# illuminated_button.net
KiCad netlist of a schematic drawn in Altium Designer
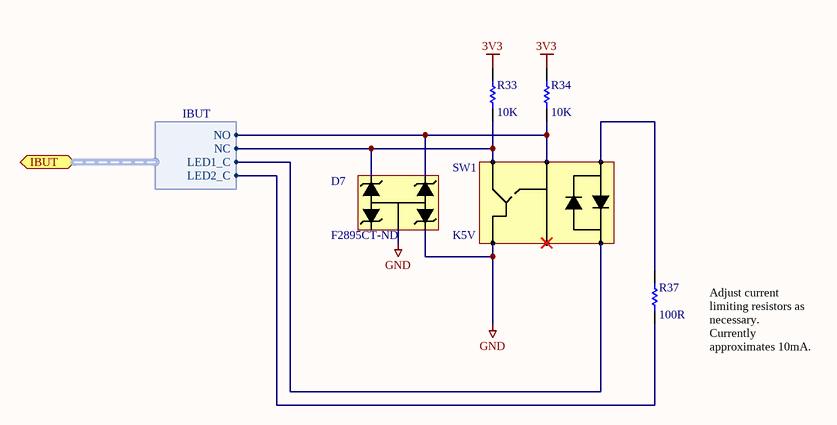
[diagram p0: illuminated_button.SchDoc]

(export (version "E")
  (design (tool "Eeschema 10.0.6"))
  (components
    (comp (ref "D7")
      (value "SP1001-04")
      (footprint "SC70-5")
      (description "8pF 15kV Unidirectional TVS Array 0.5uA@5.5V")
      (fields
        (field (name "SUPPLIER PART NUMBER 1") "F2895CT-ND")
        (field (name "MANUFACTURER") "Littelfuse Inc")
        (field (name "MANUFACTURER PART NUMBER") "SP1001-04JTG")
      )
      (libsource (lib "steve") (part "SP1001-04"))
    )
    (comp (ref "R33")
      (value "10K")
      (footprint "0603")
      (description "Semiconductor Resistor")
      (fields
        (field (name "MANUFACTURER") "TE Connectivity")
        (field (name "MANUFACTURER PART NUMBER") "1622829-1")
        (field (name "PUBLISHER") "Altium Limited")
      )
      (libsource (lib "Miscellaneous Devices") (part "Res Semi"))
    )
    (comp (ref "R34")
      (value "10K")
      (footprint "0603")
      (description "Semiconductor Resistor")
      (fields
        (field (name "MANUFACTURER") "TE Connectivity")
        (field (name "MANUFACTURER PART NUMBER") "1622829-1")
        (field (name "PUBLISHER") "Altium Limited")
      )
      (libsource (lib "Miscellaneous Devices") (part "Res Semi"))
    )
    (comp (ref "R37")
      (value "100R")
      (footprint "0603")
      (description "Semiconductor Resistor")
      (fields
        (field (name "MANUFACTURER") "Panasonic Electronic Components")
        (field (name "MANUFACTURER PART NUMBER") "ERJ-3EKF1000V")
        (field (name "PUBLISHER") "Altium Limited")
      )
      (libsource (lib "Miscellaneous Devices") (part "Res Semi"))
    )
    (comp (ref "SW1")
      (value "K5V")
      (footprint "K5V_PM")
      (description "K5V Illuminated Tactile Switch")
      (libsource (lib "steve") (part "K5V"))
    )
  )
  (nets
    (net (code "2") (name "/LED1_C") (class "Default")
      (node (ref "SW1") (pin "6") (pinfunction "6_6") (pintype "passive"))
    )
    (net (code "3") (name "/LED2_C") (class "Default")
      (node (ref "R37") (pin "1") (pinfunction "1_1") (pintype "passive"))
    )
    (net (code "4") (name "/NC") (class "Default")
      (node (ref "D7") (pin "5") (pinfunction "5_5") (pintype "passive"))
      (node (ref "R33") (pin "1") (pinfunction "1_1") (pintype "passive"))
      (node (ref "SW1") (pin "1") (pinfunction "1_1") (pintype "passive"))
    )
    (net (code "5") (name "/NO") (class "Default")
      (node (ref "D7") (pin "4") (pinfunction "4_4") (pintype "passive"))
      (node (ref "R34") (pin "1") (pinfunction "1_1") (pintype "passive"))
      (node (ref "SW1") (pin "3") (pinfunction "3_3") (pintype "passive"))
    )
    (net (code "7") (name "3V3") (class "Default")
      (node (ref "R33") (pin "2") (pinfunction "2_2") (pintype "passive"))
      (node (ref "R34") (pin "2") (pinfunction "2_2") (pintype "passive"))
    )
    (net (code "8") (name "GND") (class "Default")
      (node (ref "D7") (pin "2") (pinfunction "2_2") (pintype "passive"))
      (node (ref "D7") (pin "3") (pinfunction "3_3") (pintype "passive"))
      (node (ref "SW1") (pin "2") (pinfunction "2_2") (pintype "passive"))
    )
    (net (code "9") (name "Net-(R37-Pad2)") (class "Default")
      (node (ref "R37") (pin "2") (pinfunction "2_2") (pintype "passive"))
      (node (ref "SW1") (pin "5") (pinfunction "5_5") (pintype "passive"))
    )
    (net (code "10") (name "unconnected-(D7-Pad1)") (class "Default")
      (node (ref "D7") (pin "1") (pinfunction "1_1") (pintype "passive"))
    )
    (net (code "11") (name "unconnected-(SW1-Pad4)") (class "Default")
      (node (ref "SW1") (pin "4") (pinfunction "4_4") (pintype "passive+no_connect"))
    )
  )
)
